# lna.net
KiCad netlist of a schematic drawn in EAGLE
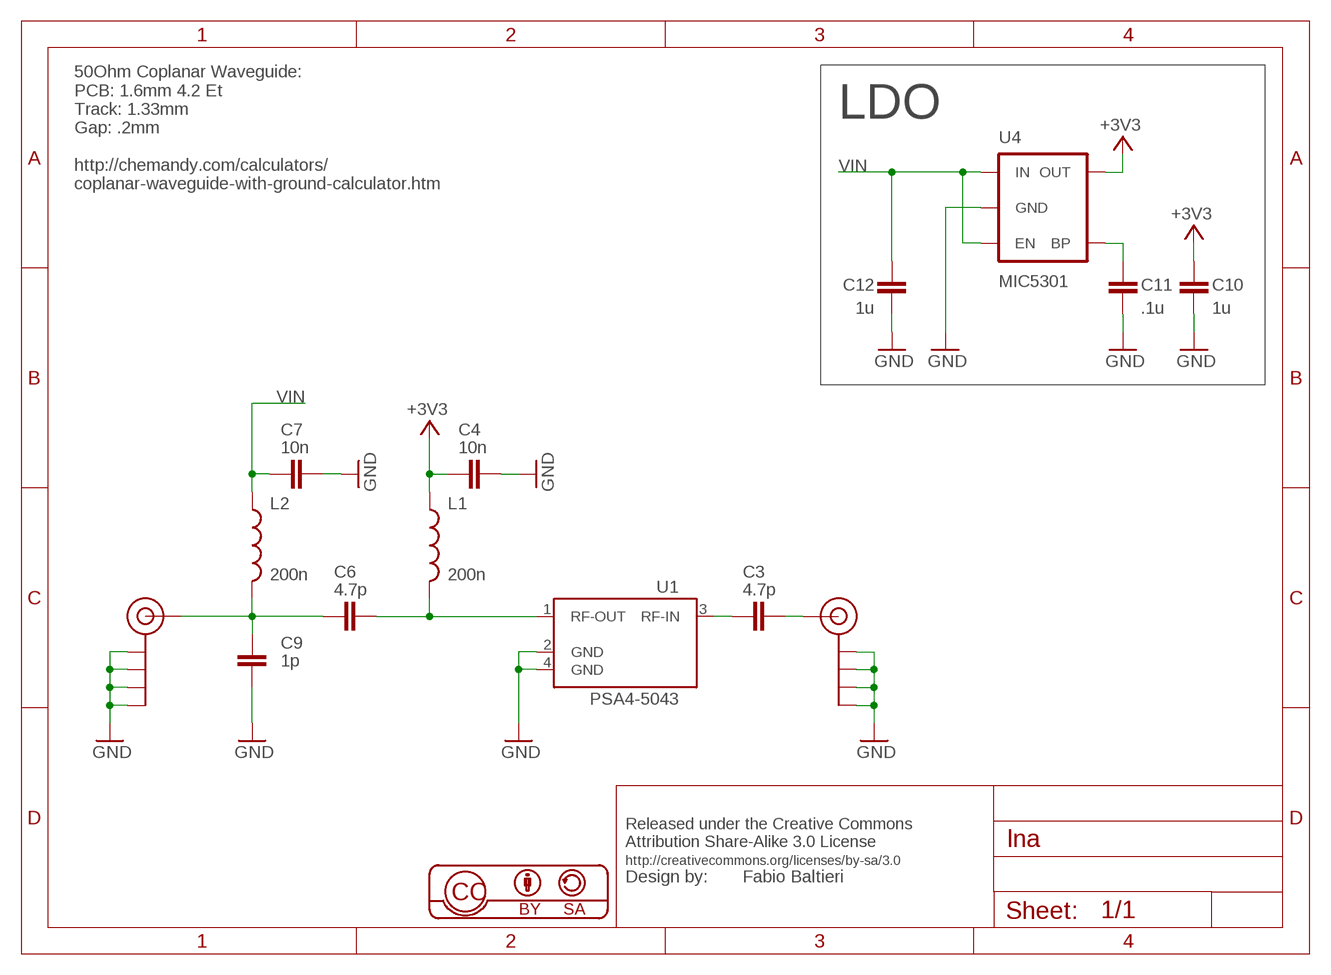
[diagram p0: schematic, sheet 1]

(export (version "E")
  (design (tool "Eeschema 10.0.6"))
  (components
    (comp (ref "C3")
      (value "4.7p")
      (footprint "eagle-import:C0603")
      (libsource (lib "eagle-import") (part "C-EUC0603"))
    )
    (comp (ref "C4")
      (value "10n")
      (footprint "eagle-import:C0603")
      (libsource (lib "eagle-import") (part "C-EUC0603"))
    )
    (comp (ref "C6")
      (value "4.7p")
      (footprint "eagle-import:C0603")
      (libsource (lib "eagle-import") (part "C-EUC0603"))
    )
    (comp (ref "C7")
      (value "10n")
      (footprint "eagle-import:C0603")
      (libsource (lib "eagle-import") (part "C-EUC0603"))
    )
    (comp (ref "C9")
      (value "1p")
      (footprint "eagle-import:C0603")
      (libsource (lib "eagle-import") (part "C-EUC0603"))
    )
    (comp (ref "C10")
      (value "1u")
      (footprint "eagle-import:C0603")
      (libsource (lib "eagle-import") (part "C-EUC0603"))
    )
    (comp (ref "C11")
      (value ".1u")
      (footprint "eagle-import:C0603")
      (libsource (lib "eagle-import") (part "C-EUC0603"))
    )
    (comp (ref "C12")
      (value "1u")
      (footprint "eagle-import:C0603")
      (libsource (lib "eagle-import") (part "C-EUC0603"))
    )
    (comp (ref "J$1")
      (value "SMA_EDGE")
      (footprint "eagle-import:SMA-EDGE")
      (libsource (lib "eagle-import") (part "SMA_EDGE"))
    )
    (comp (ref "J$2")
      (value "SMA_EDGE")
      (footprint "eagle-import:SMA-EDGE")
      (libsource (lib "eagle-import") (part "SMA_EDGE"))
    )
    (comp (ref "L1")
      (value "200n")
      (footprint "eagle-import:0603")
      (libsource (lib "eagle-import") (part "INDUCTOR0603"))
    )
    (comp (ref "L2")
      (value "200n")
      (footprint "eagle-import:0603")
      (libsource (lib "eagle-import") (part "INDUCTOR0603"))
    )
    (comp (ref "U1")
      (value "PSA4-5043")
      (footprint "eagle-import:SOT343R")
      (libsource (lib "eagle-import") (part "PSA4-5043"))
    )
    (comp (ref "U4")
      (value "MIC5301")
      (footprint "eagle-import:SOT23-5")
      (libsource (lib "eagle-import") (part "V_REG_LDOSMD"))
    )
  )
  (nets
    (net (code "1") (name "+3V3") (class "Default")
      (node (ref "C10") (pin "1") (pinfunction "1_1") (pintype "passive"))
      (node (ref "C4") (pin "1") (pinfunction "1_1") (pintype "passive"))
      (node (ref "L1") (pin "1") (pinfunction "1_1") (pintype "passive"))
      (node (ref "U4") (pin "5") (pinfunction "OUT_5") (pintype "passive"))
    )
    (net (code "2") (name "/VIN") (class "Default")
      (node (ref "C12") (pin "1") (pinfunction "1_1") (pintype "passive"))
      (node (ref "C7") (pin "1") (pinfunction "1_1") (pintype "passive"))
      (node (ref "L2") (pin "1") (pinfunction "1_1") (pintype "passive"))
      (node (ref "U4") (pin "1") (pinfunction "IN_1") (pintype "input"))
      (node (ref "U4") (pin "3") (pinfunction "EN_3") (pintype "input"))
    )
    (net (code "3") (name "GND") (class "Default")
      (node (ref "C10") (pin "2") (pinfunction "2_2") (pintype "passive"))
      (node (ref "C11") (pin "2") (pinfunction "2_2") (pintype "passive"))
      (node (ref "C12") (pin "2") (pinfunction "2_2") (pintype "passive"))
      (node (ref "C4") (pin "2") (pinfunction "2_2") (pintype "passive"))
      (node (ref "C7") (pin "2") (pinfunction "2_2") (pintype "passive"))
      (node (ref "C9") (pin "2") (pinfunction "2_2") (pintype "passive"))
      (node (ref "J$1") (pin "GND@0") (pinfunction "GND_GND@0") (pintype "bidirectional"))
      (node (ref "J$1") (pin "GND@1") (pinfunction "GND_GND@1") (pintype "bidirectional"))
      (node (ref "J$1") (pin "GND@2") (pinfunction "GND_GND@2") (pintype "bidirectional"))
      (node (ref "J$1") (pin "GND@3") (pinfunction "GND_GND@3") (pintype "bidirectional"))
      (node (ref "J$2") (pin "GND@0") (pinfunction "GND_GND@0") (pintype "bidirectional"))
      (node (ref "J$2") (pin "GND@1") (pinfunction "GND_GND@1") (pintype "bidirectional"))
      (node (ref "J$2") (pin "GND@2") (pinfunction "GND_GND@2") (pintype "bidirectional"))
      (node (ref "J$2") (pin "GND@3") (pinfunction "GND_GND@3") (pintype "bidirectional"))
      (node (ref "U1") (pin "2") (pinfunction "GND_2") (pintype "bidirectional"))
      (node (ref "U1") (pin "4") (pinfunction "GND_4") (pintype "bidirectional"))
      (node (ref "U4") (pin "2") (pinfunction "GND_2") (pintype "input"))
    )
    (net (code "4") (name "Net-(J$1-SIGNAL)") (class "Default")
      (node (ref "C6") (pin "1") (pinfunction "1_1") (pintype "passive"))
      (node (ref "C9") (pin "1") (pinfunction "1_1") (pintype "passive"))
      (node (ref "J$1") (pin "SIG") (pinfunction "SIGNAL_SIG") (pintype "bidirectional"))
      (node (ref "L2") (pin "2") (pinfunction "2_2") (pintype "passive"))
    )
    (net (code "5") (name "Net-(J$2-SIGNAL)") (class "Default")
      (node (ref "C3") (pin "2") (pinfunction "2_2") (pintype "passive"))
      (node (ref "J$2") (pin "SIG") (pinfunction "SIGNAL_SIG") (pintype "bidirectional"))
    )
    (net (code "6") (name "Net-(U1-RF-IN)") (class "Default")
      (node (ref "C3") (pin "1") (pinfunction "1_1") (pintype "passive"))
      (node (ref "U1") (pin "3") (pinfunction "RF-IN_3") (pintype "bidirectional"))
    )
    (net (code "7") (name "Net-(U1-RF-OUT)") (class "Default")
      (node (ref "C6") (pin "2") (pinfunction "2_2") (pintype "passive"))
      (node (ref "L1") (pin "2") (pinfunction "2_2") (pintype "passive"))
      (node (ref "U1") (pin "1") (pinfunction "RF-OUT_1") (pintype "bidirectional"))
    )
    (net (code "8") (name "Net-(U4-BP)") (class "Default")
      (node (ref "C11") (pin "1") (pinfunction "1_1") (pintype "passive"))
      (node (ref "U4") (pin "4") (pinfunction "BP_4") (pintype "input"))
    )
  )
)
